# Controler_2_25.net
KiCad netlist of a schematic drawn in EAGLE
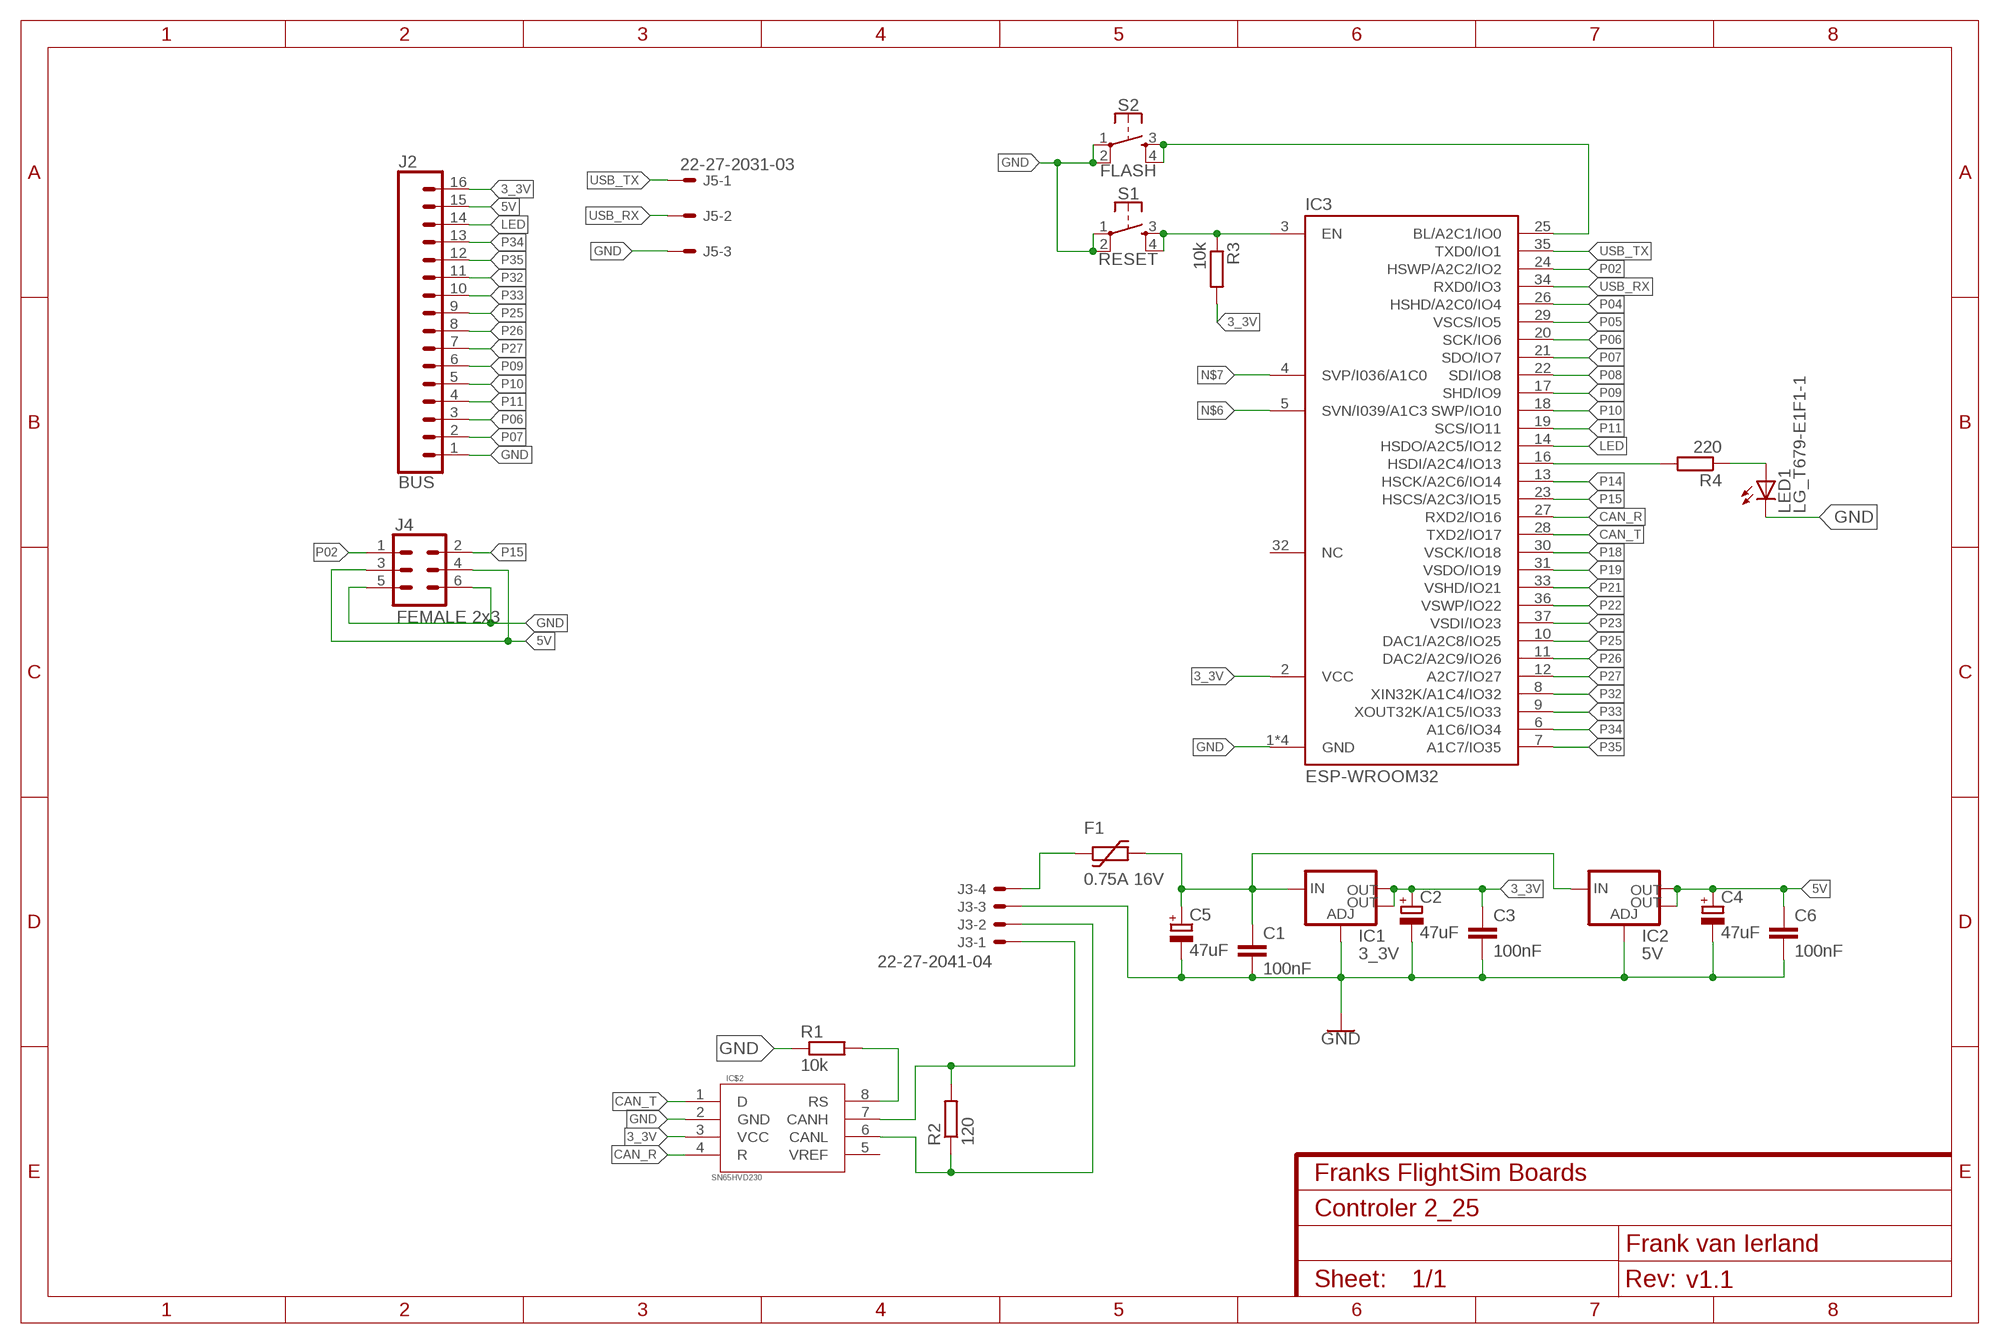
[diagram p0: schematic, sheet 1]

(export (version "E")
  (design (tool "Eeschema 10.0.6"))
  (components
    (comp (ref "C1")
      (value "100nF")
      (footprint "eagle-import:C1206")
      (libsource (lib "eagle-import") (part "C-EUC1206"))
    )
    (comp (ref "C2")
      (value "47uF")
      (footprint "eagle-import:CT3528")
      (libsource (lib "eagle-import") (part "CPOL-EUCT3528"))
    )
    (comp (ref "C3")
      (value "100nF")
      (footprint "eagle-import:C1206")
      (libsource (lib "eagle-import") (part "C-EUC1206"))
    )
    (comp (ref "C4")
      (value "47uF")
      (footprint "eagle-import:CT3528")
      (libsource (lib "eagle-import") (part "CPOL-EUCT3528"))
    )
    (comp (ref "C5")
      (value "47uF")
      (footprint "eagle-import:153CLV-0605")
      (libsource (lib "eagle-import") (part "CPOL-EU153CLV-0605"))
    )
    (comp (ref "C6")
      (value "100nF")
      (footprint "eagle-import:C1206")
      (libsource (lib "eagle-import") (part "C-EUC1206"))
    )
    (comp (ref "F1")
      (value "0.75A 16V")
      (footprint "eagle-import:1812L")
      (libsource (lib "eagle-import") (part "1812L"))
    )
    (comp (ref "IC$2")
      (value "SN65HVD230")
      (footprint "eagle-import:SO08")
      (libsource (lib "eagle-import") (part "SN65HVD230"))
    )
    (comp (ref "IC1")
      (value "3_3V")
      (footprint "eagle-import:SOT223")
      (libsource (lib "eagle-import") (part "V_REG_LM1117SOT223"))
    )
    (comp (ref "IC2")
      (value "5V")
      (footprint "eagle-import:SOT223")
      (libsource (lib "eagle-import") (part "V_REG_LM1117SOT223"))
    )
    (comp (ref "IC3")
      (value "ESP-WROOM32")
      (footprint "eagle-import:ESP-WROOM32")
      (libsource (lib "eagle-import") (part "ESP-WROOM32"))
    )
    (comp (ref "J2")
      (value "BUS")
      (footprint "eagle-import:1X16")
      (libsource (lib "eagle-import") (part "CONN_16"))
    )
    (comp (ref "J3")
      (value "22-27-2041-04")
      (footprint "eagle-import:6410-04")
      (fields (field (name "MF") "MOLEX"))
      (libsource (lib "eagle-import") (part "22-?-0427-2041"))
    )
    (comp (ref "J4")
      (value "FEMALE 2x3")
      (footprint "eagle-import:2X3")
      (libsource (lib "eagle-import") (part "CONN_03X2FEMALE"))
    )
    (comp (ref "J5")
      (value "22-27-2031-03")
      (footprint "eagle-import:6410-03")
      (fields (field (name "MF") "MOLEX"))
      (libsource (lib "eagle-import") (part "22-?-0327-2031"))
    )
    (comp (ref "LED1")
      (value "LG_T679-E1F1-1")
      (footprint "eagle-import:PLCC2")
      (libsource (lib "eagle-import") (part "_T679-?-1E1F1LG"))
    )
    (comp (ref "R1")
      (value "10k")
      (footprint "eagle-import:M1206")
      (libsource (lib "eagle-import") (part "R-EU_M1206"))
    )
    (comp (ref "R2")
      (value "120")
      (footprint "eagle-import:R1210")
      (libsource (lib "eagle-import") (part "R-EU_R1210"))
    )
    (comp (ref "R3")
      (value "10k")
      (footprint "eagle-import:M1206")
      (libsource (lib "eagle-import") (part "R-EU_M1206"))
    )
    (comp (ref "R4")
      (value "220")
      (footprint "eagle-import:M1206")
      (libsource (lib "eagle-import") (part "R-EU_M1206"))
    )
    (comp (ref "S1")
      (value "RESET")
      (footprint "eagle-import:TACTILE_SWITCH_SMD_4.6X2.8MM")
      (libsource (lib "eagle-import") (part "MOMENTARY-SWITCH-SPST-2-SMD-4.6X2.8MM"))
    )
    (comp (ref "S2")
      (value "FLASH")
      (footprint "eagle-import:TACTILE_SWITCH_SMD_4.6X2.8MM")
      (libsource (lib "eagle-import") (part "MOMENTARY-SWITCH-SPST-2-SMD-4.6X2.8MM"))
    )
  )
  (nets
    (net (code "1") (name "3_3V") (class "Default")
      (node (ref "C2") (pin "-") (pinfunction "+_-") (pintype "passive"))
      (node (ref "C3") (pin "1") (pinfunction "1_1") (pintype "passive"))
      (node (ref "IC$2") (pin "3") (pinfunction "VCC_3") (pintype "bidirectional"))
      (node (ref "IC1") (pin "2") (pinfunction "OUT_2") (pintype "output"))
      (node (ref "IC1") (pin "4") (pinfunction "OUT_4") (pintype "output"))
      (node (ref "IC3") (pin "2") (pinfunction "VCC_2") (pintype "power_in"))
      (node (ref "J2") (pin "16") (pinfunction "16_16") (pintype "passive"))
      (node (ref "R3") (pin "2") (pinfunction "2_2") (pintype "passive"))
    )
    (net (code "2") (name "5V") (class "Default")
      (node (ref "C4") (pin "-") (pinfunction "+_-") (pintype "passive"))
      (node (ref "C6") (pin "1") (pinfunction "1_1") (pintype "passive"))
      (node (ref "IC2") (pin "2") (pinfunction "OUT_2") (pintype "output"))
      (node (ref "IC2") (pin "4") (pinfunction "OUT_4") (pintype "output"))
      (node (ref "J2") (pin "15") (pinfunction "15_15") (pintype "passive"))
      (node (ref "J4") (pin "3") (pinfunction "3_3") (pintype "bidirectional"))
      (node (ref "J4") (pin "4") (pinfunction "4_4") (pintype "bidirectional"))
    )
    (net (code "3") (name "CAN_R") (class "Default")
      (node (ref "IC$2") (pin "4") (pinfunction "R_4") (pintype "bidirectional"))
      (node (ref "IC3") (pin "27") (pinfunction "RXD2/IO16_27") (pintype "bidirectional"))
    )
    (net (code "4") (name "CAN_T") (class "Default")
      (node (ref "IC$2") (pin "1") (pinfunction "D_1") (pintype "bidirectional"))
      (node (ref "IC3") (pin "28") (pinfunction "TXD2/IO17_28") (pintype "bidirectional"))
    )
    (net (code "5") (name "GND") (class "Default")
      (node (ref "C1") (pin "2") (pinfunction "2_2") (pintype "passive"))
      (node (ref "C2") (pin "+") (pinfunction "-_+") (pintype "passive"))
      (node (ref "C3") (pin "2") (pinfunction "2_2") (pintype "passive"))
      (node (ref "C4") (pin "+") (pinfunction "-_+") (pintype "passive"))
      (node (ref "C5") (pin "-") (pinfunction "-_-") (pintype "passive"))
      (node (ref "C6") (pin "2") (pinfunction "2_2") (pintype "passive"))
      (node (ref "IC$2") (pin "2") (pinfunction "GND_2") (pintype "bidirectional"))
      (node (ref "IC1") (pin "1") (pinfunction "ADJ_1") (pintype "input"))
      (node (ref "IC2") (pin "1") (pinfunction "ADJ_1") (pintype "input"))
      (node (ref "IC3") (pin "1") (pinfunction "GND_1") (pintype "power_in"))
      (node (ref "IC3") (pin "15") (pinfunction "GND_15") (pintype "power_in"))
      (node (ref "IC3") (pin "38") (pinfunction "GND_38") (pintype "power_in"))
      (node (ref "IC3") (pin "TP") (pinfunction "GND_TP") (pintype "power_in"))
      (node (ref "J2") (pin "1") (pinfunction "1_1") (pintype "passive"))
      (node (ref "J3") (pin "3") (pinfunction "S_3") (pintype "passive"))
      (node (ref "J4") (pin "5") (pinfunction "5_5") (pintype "bidirectional"))
      (node (ref "J4") (pin "6") (pinfunction "6_6") (pintype "bidirectional"))
      (node (ref "J5") (pin "3") (pinfunction "S_3") (pintype "passive"))
      (node (ref "LED1") (pin "C") (pinfunction "C_C") (pintype "passive"))
      (node (ref "R1") (pin "1") (pinfunction "1_1") (pintype "passive"))
      (node (ref "S1") (pin "1") (pinfunction "1_1") (pintype "passive"))
      (node (ref "S1") (pin "2") (pinfunction "2_2") (pintype "passive"))
      (node (ref "S2") (pin "1") (pinfunction "1_1") (pintype "passive"))
      (node (ref "S2") (pin "2") (pinfunction "2_2") (pintype "passive"))
    )
    (net (code "6") (name "LED") (class "Default")
      (node (ref "IC3") (pin "14") (pinfunction "HSDO/A2C5/IO12_14") (pintype "bidirectional"))
      (node (ref "J2") (pin "14") (pinfunction "14_14") (pintype "passive"))
    )
    (net (code "7") (name "N$6") (class "Default")
      (node (ref "IC3") (pin "5") (pinfunction "SVN/I039/A1C3_5") (pintype "bidirectional"))
    )
    (net (code "8") (name "N$7") (class "Default")
      (node (ref "IC3") (pin "4") (pinfunction "SVP/I036/A1C0_4") (pintype "bidirectional"))
    )
    (net (code "9") (name "Net-(IC$2-CANH)") (class "Default")
      (node (ref "IC$2") (pin "7") (pinfunction "CANH_7") (pintype "bidirectional"))
      (node (ref "J3") (pin "1") (pinfunction "S_1") (pintype "passive"))
      (node (ref "R2") (pin "2") (pinfunction "2_2") (pintype "passive"))
    )
    (net (code "10") (name "Net-(IC$2-CANL)") (class "Default")
      (node (ref "IC$2") (pin "6") (pinfunction "CANL_6") (pintype "bidirectional"))
      (node (ref "J3") (pin "2") (pinfunction "S_2") (pintype "passive"))
      (node (ref "R2") (pin "1") (pinfunction "1_1") (pintype "passive"))
    )
    (net (code "11") (name "Net-(IC$2-RS)") (class "Default")
      (node (ref "IC$2") (pin "8") (pinfunction "RS_8") (pintype "bidirectional"))
      (node (ref "R1") (pin "2") (pinfunction "2_2") (pintype "passive"))
    )
    (net (code "12") (name "Net-(IC1-IN)") (class "Default")
      (node (ref "C1") (pin "1") (pinfunction "1_1") (pintype "passive"))
      (node (ref "C5") (pin "+") (pinfunction "+_+") (pintype "passive"))
      (node (ref "F1") (pin "2") (pinfunction "2_2") (pintype "passive"))
      (node (ref "IC1") (pin "3") (pinfunction "IN_3") (pintype "input"))
      (node (ref "IC2") (pin "3") (pinfunction "IN_3") (pintype "input"))
    )
    (net (code "13") (name "Net-(IC3-BL{slash}A2C1{slash}IO0)") (class "Default")
      (node (ref "IC3") (pin "25") (pinfunction "BL/A2C1/IO0_25") (pintype "bidirectional"))
      (node (ref "S2") (pin "3") (pinfunction "3_3") (pintype "passive"))
      (node (ref "S2") (pin "4") (pinfunction "4_4") (pintype "passive"))
    )
    (net (code "14") (name "Net-(IC3-EN)") (class "Default")
      (node (ref "IC3") (pin "3") (pinfunction "EN_3") (pintype "bidirectional"))
      (node (ref "R3") (pin "1") (pinfunction "1_1") (pintype "passive"))
      (node (ref "S1") (pin "3") (pinfunction "3_3") (pintype "passive"))
      (node (ref "S1") (pin "4") (pinfunction "4_4") (pintype "passive"))
    )
    (net (code "15") (name "Net-(IC3-HSDI{slash}A2C4{slash}IO13)") (class "Default")
      (node (ref "IC3") (pin "16") (pinfunction "HSDI/A2C4/IO13_16") (pintype "bidirectional"))
      (node (ref "R4") (pin "2") (pinfunction "2_2") (pintype "passive"))
    )
    (net (code "16") (name "Net-(J3D-S)") (class "Default")
      (node (ref "F1") (pin "1") (pinfunction "1_1") (pintype "passive"))
      (node (ref "J3") (pin "4") (pinfunction "S_4") (pintype "passive"))
    )
    (net (code "17") (name "Net-(LED1-PadA)") (class "Default")
      (node (ref "LED1") (pin "A") (pinfunction "A_A") (pintype "passive"))
      (node (ref "R4") (pin "1") (pinfunction "1_1") (pintype "passive"))
    )
    (net (code "18") (name "P02") (class "Default")
      (node (ref "IC3") (pin "24") (pinfunction "HSWP/A2C2/IO2_24") (pintype "bidirectional"))
      (node (ref "J4") (pin "1") (pinfunction "1_1") (pintype "bidirectional"))
    )
    (net (code "19") (name "P04") (class "Default")
      (node (ref "IC3") (pin "26") (pinfunction "HSHD/A2C0/IO4_26") (pintype "bidirectional"))
    )
    (net (code "20") (name "P05") (class "Default")
      (node (ref "IC3") (pin "29") (pinfunction "VSCS/IO5_29") (pintype "bidirectional"))
    )
    (net (code "21") (name "P06") (class "Default")
      (node (ref "IC3") (pin "20") (pinfunction "SCK/IO6_20") (pintype "bidirectional"))
      (node (ref "J2") (pin "3") (pinfunction "3_3") (pintype "passive"))
    )
    (net (code "22") (name "P07") (class "Default")
      (node (ref "IC3") (pin "21") (pinfunction "SDO/IO7_21") (pintype "bidirectional"))
      (node (ref "J2") (pin "2") (pinfunction "2_2") (pintype "passive"))
    )
    (net (code "23") (name "P08") (class "Default")
      (node (ref "IC3") (pin "22") (pinfunction "SDI/IO8_22") (pintype "bidirectional"))
    )
    (net (code "24") (name "P09") (class "Default")
      (node (ref "IC3") (pin "17") (pinfunction "SHD/IO9_17") (pintype "bidirectional"))
      (node (ref "J2") (pin "6") (pinfunction "6_6") (pintype "passive"))
    )
    (net (code "25") (name "P10") (class "Default")
      (node (ref "IC3") (pin "18") (pinfunction "SWP/IO10_18") (pintype "bidirectional"))
      (node (ref "J2") (pin "5") (pinfunction "5_5") (pintype "passive"))
    )
    (net (code "26") (name "P11") (class "Default")
      (node (ref "IC3") (pin "19") (pinfunction "SCS/IO11_19") (pintype "bidirectional"))
      (node (ref "J2") (pin "4") (pinfunction "4_4") (pintype "passive"))
    )
    (net (code "27") (name "P14") (class "Default")
      (node (ref "IC3") (pin "13") (pinfunction "HSCK/A2C6/IO14_13") (pintype "bidirectional"))
    )
    (net (code "28") (name "P15") (class "Default")
      (node (ref "IC3") (pin "23") (pinfunction "HSCS/A2C3/IO15_23") (pintype "bidirectional"))
      (node (ref "J4") (pin "2") (pinfunction "2_2") (pintype "bidirectional"))
    )
    (net (code "29") (name "P18") (class "Default")
      (node (ref "IC3") (pin "30") (pinfunction "VSCK/IO18_30") (pintype "bidirectional"))
    )
    (net (code "30") (name "P19") (class "Default")
      (node (ref "IC3") (pin "31") (pinfunction "VSDO/IO19_31") (pintype "bidirectional"))
    )
    (net (code "31") (name "P21") (class "Default")
      (node (ref "IC3") (pin "33") (pinfunction "VSHD/IO21_33") (pintype "bidirectional"))
    )
    (net (code "32") (name "P22") (class "Default")
      (node (ref "IC3") (pin "36") (pinfunction "VSWP/IO22_36") (pintype "bidirectional"))
    )
    (net (code "33") (name "P23") (class "Default")
      (node (ref "IC3") (pin "37") (pinfunction "VSDI/IO23_37") (pintype "bidirectional"))
    )
    (net (code "34") (name "P25") (class "Default")
      (node (ref "IC3") (pin "10") (pinfunction "DAC1/A2C8/IO25_10") (pintype "bidirectional"))
      (node (ref "J2") (pin "9") (pinfunction "9_9") (pintype "passive"))
    )
    (net (code "35") (name "P26") (class "Default")
      (node (ref "IC3") (pin "11") (pinfunction "DAC2/A2C9/IO26_11") (pintype "bidirectional"))
      (node (ref "J2") (pin "8") (pinfunction "8_8") (pintype "passive"))
    )
    (net (code "36") (name "P27") (class "Default")
      (node (ref "IC3") (pin "12") (pinfunction "A2C7/IO27_12") (pintype "bidirectional"))
      (node (ref "J2") (pin "7") (pinfunction "7_7") (pintype "passive"))
    )
    (net (code "37") (name "P32") (class "Default")
      (node (ref "IC3") (pin "8") (pinfunction "XIN32K/A1C4/IO32_8") (pintype "bidirectional"))
      (node (ref "J2") (pin "11") (pinfunction "11_11") (pintype "passive"))
    )
    (net (code "38") (name "P33") (class "Default")
      (node (ref "IC3") (pin "9") (pinfunction "XOUT32K/A1C5/IO33_9") (pintype "bidirectional"))
      (node (ref "J2") (pin "10") (pinfunction "10_10") (pintype "passive"))
    )
    (net (code "39") (name "P34") (class "Default")
      (node (ref "IC3") (pin "6") (pinfunction "A1C6/IO34_6") (pintype "bidirectional"))
      (node (ref "J2") (pin "13") (pinfunction "13_13") (pintype "passive"))
    )
    (net (code "40") (name "P35") (class "Default")
      (node (ref "IC3") (pin "7") (pinfunction "A1C7/IO35_7") (pintype "bidirectional"))
      (node (ref "J2") (pin "12") (pinfunction "12_12") (pintype "passive"))
    )
    (net (code "41") (name "USB_RX") (class "Default")
      (node (ref "IC3") (pin "34") (pinfunction "RXD0/IO3_34") (pintype "bidirectional"))
      (node (ref "J5") (pin "2") (pinfunction "S_2") (pintype "passive"))
    )
    (net (code "42") (name "USB_TX") (class "Default")
      (node (ref "IC3") (pin "35") (pinfunction "TXD0/IO1_35") (pintype "bidirectional"))
      (node (ref "J5") (pin "1") (pinfunction "S_1") (pintype "passive"))
    )
    (net (code "43") (name "unconnected-(IC$2-VREF-Pad5)") (class "Default")
      (node (ref "IC$2") (pin "5") (pinfunction "VREF_5") (pintype "bidirectional"))
    )
    (net (code "44") (name "unconnected-(IC3-NC-Pad32)") (class "Default")
      (node (ref "IC3") (pin "32") (pinfunction "NC_32") (pintype "bidirectional"))
    )
  )
)
